# DB10011_USBToSerial.net
KiCad netlist of a schematic drawn in Altium Designer
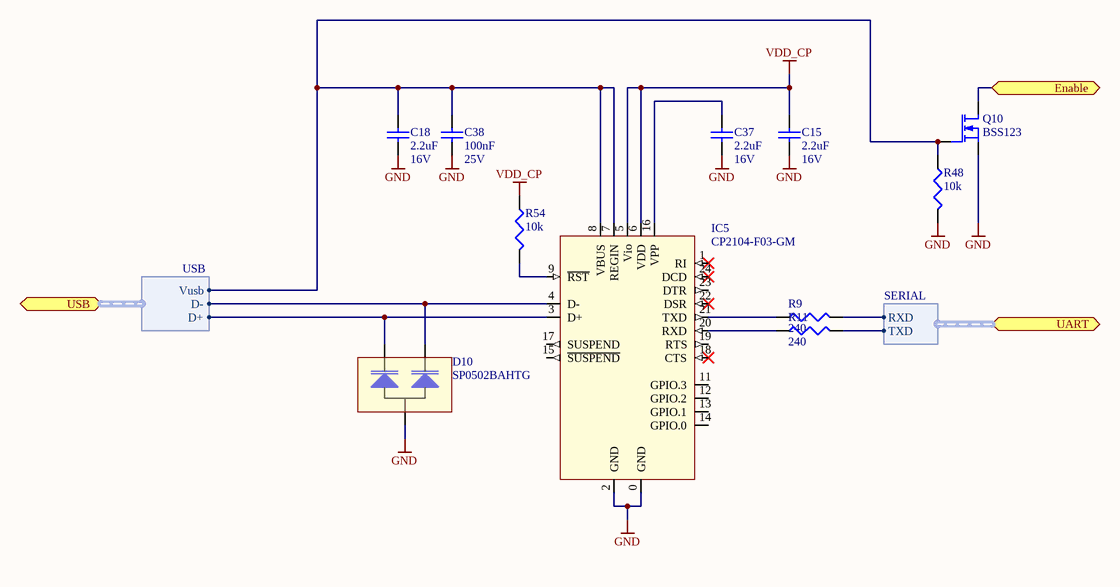
[diagram p0: DB10011_USBToSerial.SchDoc]

(export (version "E")
  (design (tool "Eeschema 10.0.6"))
  (components
    (comp (ref "C15")
      (value "2.2uF")
      (footprint "C0603")
      (description "Capacitor, 2.2uF, 16V, X5R")
      (fields (field (name "VOLTAGE RATING") "16V"))
      (libsource (lib "AR_Capacitors_Ceramic") (part "2.2uF/0603/CER/16V"))
    )
    (comp (ref "C18")
      (value "2.2uF")
      (footprint "C0603")
      (description "Capacitor, 2.2uF, 16V, X5R")
      (fields (field (name "VOLTAGE RATING") "16V"))
      (libsource (lib "AR_Capacitors_Ceramic") (part "2.2uF/0603/CER/16V"))
    )
    (comp (ref "C37")
      (value "2.2uF")
      (footprint "C0603")
      (description "Capacitor, 2.2uF, 16V, X5R")
      (fields (field (name "VOLTAGE RATING") "16V"))
      (libsource (lib "AR_Capacitors_Ceramic") (part "2.2uF/0603/CER/16V"))
    )
    (comp (ref "C38")
      (value "100nF")
      (footprint "C0402")
      (description "Capacitor, 100nF, 25V, X7R")
      (fields (field (name "VOLTAGE RATING") "25V"))
      (libsource (lib "AR_Capacitors_Ceramic") (part "100nF/0402/CER/25V"))
    )
    (comp (ref "D10")
      (value "SP0502BAHTG")
      (footprint "SOT23")
      (description "Diode TVS Dual, Vrwm: 5.5V Vc: 8V")
      (libsource (lib "AR_Diodes") (part "SP0502BAHTG"))
    )
    (comp (ref "IC5")
      (value "CP2104-F03-GM")
      (footprint "QFN24")
      (description "USB to UART converter")
      (libsource (lib "AR_ICs") (part "CP2104-F03-GM"))
    )
    (comp (ref "Q10")
      (value "BSS123")
      (footprint "SOT-23")
      (description "Mosfet, N-channel, Vds:100V, Id:0.15A, Vgs-th:2.8V, Rds-on:3.5ohm")
      (libsource (lib "AR_Mosfets") (part "BSS123"))
    )
    (comp (ref "R9")
      (value "240")
      (footprint "0402")
      (description "Resistor, 240, 0.1%, 0.0625W, 50V, 100PPM, 0402")
      (libsource (lib "AR_Resistors_SMD") (part "240/0402/0063W/50V"))
    )
    (comp (ref "R11")
      (value "240")
      (footprint "0402")
      (description "Resistor, 240, 0.1%, 0.0625W, 50V, 100PPM, 0402")
      (libsource (lib "AR_Resistors_SMD") (part "240/0402/0063W/50V"))
    )
    (comp (ref "R48")
      (value "10k")
      (footprint "0402")
      (description "Resistor, 10k, 0.1%, 0.0625W, 50V, 100PPM, 0402")
      (libsource (lib "AR_Resistors_SMD") (part "10k/0402/0063W/50V"))
    )
    (comp (ref "R54")
      (value "10k")
      (footprint "0402")
      (description "Resistor, 10k, 0.1%, 0.0625W, 50V, 100PPM, 0402")
      (libsource (lib "AR_Resistors_SMD") (part "10k/0402/0063W/50V"))
    )
  )
  (nets
    (net (code "3") (name "/D+") (class "Default")
      (node (ref "D10") (pin "K2") (pinfunction "K2_K2") (pintype "passive"))
      (node (ref "IC5") (pin "3") (pinfunction "D+_3") (pintype "bidirectional"))
    )
    (net (code "4") (name "/D-") (class "Default")
      (node (ref "D10") (pin "K1") (pinfunction "K1_K1") (pintype "passive"))
      (node (ref "IC5") (pin "4") (pinfunction "D-_4") (pintype "bidirectional"))
    )
    (net (code "5") (name "/Enable") (class "Default")
      (node (ref "Q10") (pin "D") (pinfunction "D_D") (pintype "passive"))
    )
    (net (code "6") (name "/RXD") (class "Default")
      (node (ref "R9") (pin "1") (pinfunction "1_1") (pintype "passive"))
    )
    (net (code "7") (name "/TXD") (class "Default")
      (node (ref "R11") (pin "1") (pinfunction "1_1") (pintype "passive"))
    )
    (net (code "8") (name "/Vusb") (class "Default")
      (node (ref "C18") (pin "2") (pinfunction "2_2") (pintype "passive"))
      (node (ref "C38") (pin "2") (pinfunction "2_2") (pintype "passive"))
      (node (ref "IC5") (pin "7") (pinfunction "REGIN_7") (pintype "power_in"))
      (node (ref "IC5") (pin "8") (pinfunction "VBUS_8") (pintype "power_in"))
      (node (ref "Q10") (pin "G") (pinfunction "G_G") (pintype "passive"))
      (node (ref "R48") (pin "2") (pinfunction "2_2") (pintype "passive"))
    )
    (net (code "11") (name "GND") (class "Default")
      (node (ref "C15") (pin "1") (pinfunction "1_1") (pintype "passive"))
      (node (ref "C18") (pin "1") (pinfunction "1_1") (pintype "passive"))
      (node (ref "C37") (pin "1") (pinfunction "1_1") (pintype "passive"))
      (node (ref "C38") (pin "1") (pinfunction "1_1") (pintype "passive"))
      (node (ref "D10") (pin "A") (pinfunction "A_A") (pintype "passive"))
      (node (ref "IC5") (pin "0") (pinfunction "GND_0") (pintype "power_in"))
      (node (ref "IC5") (pin "2") (pinfunction "GND_2") (pintype "power_in"))
      (node (ref "Q10") (pin "S") (pinfunction "S_S") (pintype "passive"))
      (node (ref "R48") (pin "1") (pinfunction "1_1") (pintype "passive"))
    )
    (net (code "12") (name "Net-(IC5-RXD)") (class "Default")
      (node (ref "IC5") (pin "20") (pinfunction "RXD_20") (pintype "input"))
      (node (ref "R11") (pin "2") (pinfunction "2_2") (pintype "passive"))
    )
    (net (code "13") (name "Net-(IC5-TXD)") (class "Default")
      (node (ref "IC5") (pin "21") (pinfunction "TXD_21") (pintype "output"))
      (node (ref "R9") (pin "2") (pinfunction "2_2") (pintype "passive"))
    )
    (net (code "14") (name "Net-(IC5-VPP)") (class "Default")
      (node (ref "C37") (pin "2") (pinfunction "2_2") (pintype "passive"))
      (node (ref "IC5") (pin "16") (pinfunction "VPP_16") (pintype "power_in"))
    )
    (net (code "15") (name "Net-(IC5-~{RST})") (class "Default")
      (node (ref "IC5") (pin "9") (pinfunction "~{RST}_9") (pintype "input"))
      (node (ref "R54") (pin "1") (pinfunction "1_1") (pintype "passive"))
    )
    (net (code "16") (name "VDD_CP") (class "Default")
      (node (ref "C15") (pin "2") (pinfunction "2_2") (pintype "passive"))
      (node (ref "IC5") (pin "5") (pinfunction "Vio_5") (pintype "passive"))
      (node (ref "IC5") (pin "6") (pinfunction "VDD_6") (pintype "power_in"))
      (node (ref "R54") (pin "2") (pinfunction "2_2") (pintype "passive"))
    )
    (net (code "17") (name "unconnected-(IC5-CTS-Pad18)") (class "Default")
      (node (ref "IC5") (pin "18") (pinfunction "CTS_18") (pintype "input+no_connect"))
    )
    (net (code "18") (name "unconnected-(IC5-DCD-Pad24)") (class "Default")
      (node (ref "IC5") (pin "24") (pinfunction "DCD_24") (pintype "input+no_connect"))
    )
    (net (code "19") (name "unconnected-(IC5-DSR-Pad22)") (class "Default")
      (node (ref "IC5") (pin "22") (pinfunction "DSR_22") (pintype "input+no_connect"))
    )
    (net (code "20") (name "unconnected-(IC5-DTR-Pad23)") (class "Default")
      (node (ref "IC5") (pin "23") (pinfunction "DTR_23") (pintype "output"))
    )
    (net (code "21") (name "unconnected-(IC5-GPIO.0-Pad14)") (class "Default")
      (node (ref "IC5") (pin "14") (pinfunction "GPIO.0_14") (pintype "passive"))
    )
    (net (code "22") (name "unconnected-(IC5-GPIO.1-Pad13)") (class "Default")
      (node (ref "IC5") (pin "13") (pinfunction "GPIO.1_13") (pintype "passive"))
    )
    (net (code "23") (name "unconnected-(IC5-GPIO.2-Pad12)") (class "Default")
      (node (ref "IC5") (pin "12") (pinfunction "GPIO.2_12") (pintype "passive"))
    )
    (net (code "24") (name "unconnected-(IC5-GPIO.3-Pad11)") (class "Default")
      (node (ref "IC5") (pin "11") (pinfunction "GPIO.3_11") (pintype "passive"))
    )
    (net (code "25") (name "unconnected-(IC5-RI-Pad1)") (class "Default")
      (node (ref "IC5") (pin "1") (pinfunction "RI_1") (pintype "input+no_connect"))
    )
    (net (code "26") (name "unconnected-(IC5-RTS-Pad19)") (class "Default")
      (node (ref "IC5") (pin "19") (pinfunction "RTS_19") (pintype "output"))
    )
    (net (code "27") (name "unconnected-(IC5-SUSPEND-Pad17)") (class "Default")
      (node (ref "IC5") (pin "17") (pinfunction "SUSPEND_17") (pintype "output"))
    )
    (net (code "28") (name "unconnected-(IC5-~{SUSPEND}-Pad15)") (class "Default")
      (node (ref "IC5") (pin "15") (pinfunction "~{SUSPEND}_15") (pintype "output"))
    )
  )
)
